# ESP8266-SeeedBreakoutBoard.net
KiCad netlist of a schematic drawn in EAGLE
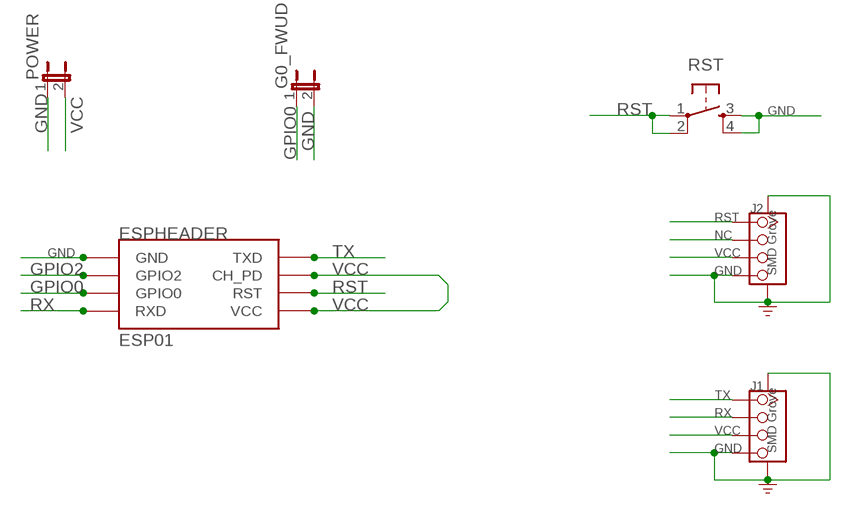
[diagram p0: schematic, sheet 1]

(export (version "E")
  (design (tool "Eeschema 10.0.6"))
  (components
    (comp (ref "ESPHEADER")
      (value "ESP01")
      (footprint "eagle-import:ESP01")
      (libsource (lib "eagle-import") (part "ESP01"))
    )
    (comp (ref "G0_FWUD")
      (value "JUMPER-2PTH")
      (footprint "eagle-import:1X02")
      (libsource (lib "eagle-import") (part "JUMPER-2PTH"))
    )
    (comp (ref "J1")
      (value "SMD Grove")
      (footprint "eagle-import:4P-SMD-2.0")
      (libsource (lib "eagle-import") (part "TWIG-4P-2.0-SMD-FEMALE-REINFORCE'DD'"))
    )
    (comp (ref "J2")
      (value "SMD Grove")
      (footprint "eagle-import:4P-SMD-2.0")
      (libsource (lib "eagle-import") (part "TWIG-4P-2.0-SMD-FEMALE-REINFORCE'DD'"))
    )
    (comp (ref "POWER")
      (value "JUMPER-2PTH")
      (footprint "eagle-import:1X02")
      (libsource (lib "eagle-import") (part "JUMPER-2PTH"))
    )
    (comp (ref "RST")
      (value "TAC_SWITCHPTH")
      (footprint "eagle-import:TACTILE-PTH")
      (libsource (lib "eagle-import") (part "TAC_SWITCHPTH"))
    )
  )
  (nets
    (net (code "1") (name "/GPIO0") (class "Default")
      (node (ref "ESPHEADER") (pin "GPIO0") (pinfunction "GPIO0_GPIO0") (pintype "bidirectional"))
      (node (ref "G0_FWUD") (pin "1") (pinfunction "1_1") (pintype "passive"))
    )
    (net (code "2") (name "/GPIO2") (class "Default")
      (node (ref "ESPHEADER") (pin "GPIO2") (pinfunction "GPIO2_GPIO2") (pintype "bidirectional"))
    )
    (net (code "3") (name "/NC") (class "Default")
      (node (ref "J2") (pin "2") (pinfunction "2_2") (pintype "bidirectional"))
    )
    (net (code "4") (name "/RST") (class "Default")
      (node (ref "ESPHEADER") (pin "RST") (pinfunction "RST_RST") (pintype "bidirectional"))
      (node (ref "J2") (pin "1") (pinfunction "1_1") (pintype "bidirectional"))
      (node (ref "RST") (pin "1") (pinfunction "1_1") (pintype "passive"))
      (node (ref "RST") (pin "2") (pinfunction "2_2") (pintype "passive"))
    )
    (net (code "5") (name "/RX") (class "Default")
      (node (ref "ESPHEADER") (pin "RX") (pinfunction "RXD_RX") (pintype "bidirectional"))
      (node (ref "J1") (pin "2") (pinfunction "2_2") (pintype "bidirectional"))
    )
    (net (code "6") (name "/TX") (class "Default")
      (node (ref "ESPHEADER") (pin "TX") (pinfunction "TXD_TX") (pintype "bidirectional"))
      (node (ref "J1") (pin "1") (pinfunction "1_1") (pintype "bidirectional"))
    )
    (net (code "7") (name "/VCC") (class "Default")
      (node (ref "ESPHEADER") (pin "CH_PD") (pinfunction "CH_PD_CH_PD") (pintype "bidirectional"))
      (node (ref "ESPHEADER") (pin "VCC") (pinfunction "VCC_VCC") (pintype "bidirectional"))
      (node (ref "J1") (pin "3") (pinfunction "3_3") (pintype "bidirectional"))
      (node (ref "J2") (pin "3") (pinfunction "3_3") (pintype "bidirectional"))
      (node (ref "POWER") (pin "2") (pinfunction "2_2") (pintype "passive"))
    )
    (net (code "8") (name "GND_POWER") (class "Default")
      (node (ref "ESPHEADER") (pin "GND") (pinfunction "GND_GND") (pintype "bidirectional"))
      (node (ref "G0_FWUD") (pin "2") (pinfunction "2_2") (pintype "passive"))
      (node (ref "J1") (pin "4") (pinfunction "4_4") (pintype "bidirectional"))
      (node (ref "J1") (pin "SS1") (pinfunction "SS1_SS1") (pintype "bidirectional"))
      (node (ref "J1") (pin "SS2") (pinfunction "SS2_SS2") (pintype "bidirectional"))
      (node (ref "J2") (pin "4") (pinfunction "4_4") (pintype "bidirectional"))
      (node (ref "J2") (pin "SS1") (pinfunction "SS1_SS1") (pintype "bidirectional"))
      (node (ref "J2") (pin "SS2") (pinfunction "SS2_SS2") (pintype "bidirectional"))
      (node (ref "POWER") (pin "1") (pinfunction "1_1") (pintype "passive"))
      (node (ref "RST") (pin "3") (pinfunction "3_3") (pintype "passive"))
      (node (ref "RST") (pin "4") (pinfunction "4_4") (pintype "passive"))
    )
  )
)
